# sub_sys_pdu.net
KiCad netlist of a schematic drawn in EAGLE
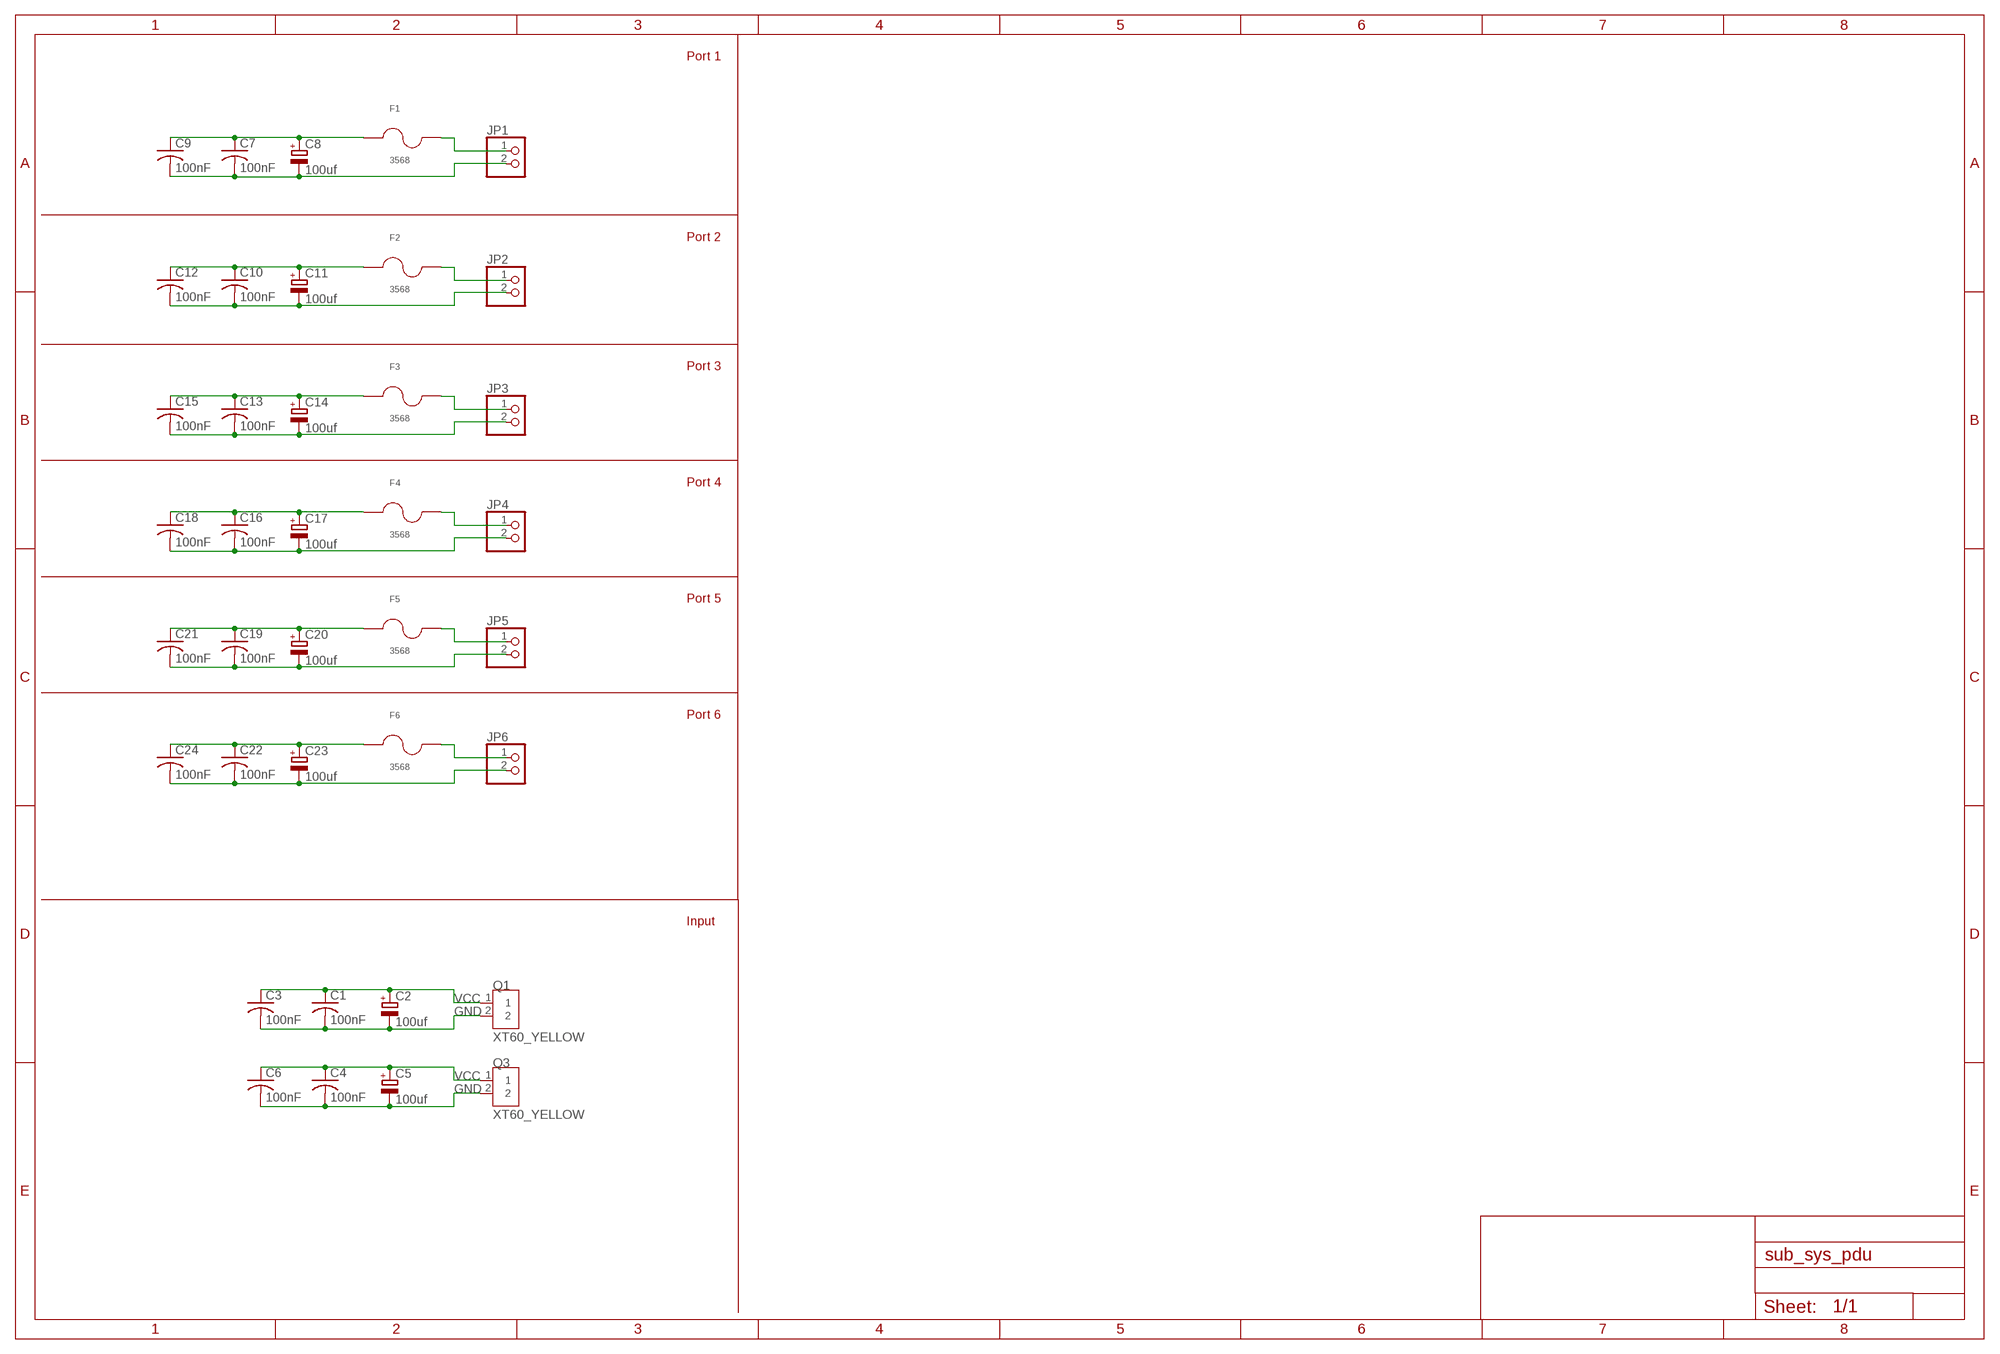
[diagram p0: schematic, sheet 1]

(export (version "E")
  (design (tool "Eeschema 10.0.6"))
  (components
    (comp (ref "C1")
      (value "100nF")
      (footprint "eagle-import:C0805")
      (libsource (lib "eagle-import") (part "C-USC0805"))
    )
    (comp (ref "C2")
      (value "100uf")
      (footprint "eagle-import:E5-10,5")
      (libsource (lib "eagle-import") (part "CPOL-EUE5-10.5"))
    )
    (comp (ref "C3")
      (value "100nF")
      (footprint "eagle-import:C0805")
      (libsource (lib "eagle-import") (part "C-USC0805"))
    )
    (comp (ref "C4")
      (value "100nF")
      (footprint "eagle-import:C0805")
      (libsource (lib "eagle-import") (part "C-USC0805"))
    )
    (comp (ref "C5")
      (value "100uf")
      (footprint "eagle-import:E5-10,5")
      (libsource (lib "eagle-import") (part "CPOL-EUE5-10.5"))
    )
    (comp (ref "C6")
      (value "100nF")
      (footprint "eagle-import:C0805")
      (libsource (lib "eagle-import") (part "C-USC0805"))
    )
    (comp (ref "C7")
      (value "100nF")
      (footprint "eagle-import:C0805")
      (libsource (lib "eagle-import") (part "C-USC0805"))
    )
    (comp (ref "C8")
      (value "100uf")
      (footprint "eagle-import:E5-10,5")
      (libsource (lib "eagle-import") (part "CPOL-EUE5-10.5"))
    )
    (comp (ref "C9")
      (value "100nF")
      (footprint "eagle-import:C0805")
      (libsource (lib "eagle-import") (part "C-USC0805"))
    )
    (comp (ref "C10")
      (value "100nF")
      (footprint "eagle-import:C0805")
      (libsource (lib "eagle-import") (part "C-USC0805"))
    )
    (comp (ref "C11")
      (value "100uf")
      (footprint "eagle-import:E5-10,5")
      (libsource (lib "eagle-import") (part "CPOL-EUE5-10.5"))
    )
    (comp (ref "C12")
      (value "100nF")
      (footprint "eagle-import:C0805")
      (libsource (lib "eagle-import") (part "C-USC0805"))
    )
    (comp (ref "C13")
      (value "100nF")
      (footprint "eagle-import:C0805")
      (libsource (lib "eagle-import") (part "C-USC0805"))
    )
    (comp (ref "C14")
      (value "100uf")
      (footprint "eagle-import:E5-10,5")
      (libsource (lib "eagle-import") (part "CPOL-EUE5-10.5"))
    )
    (comp (ref "C15")
      (value "100nF")
      (footprint "eagle-import:C0805")
      (libsource (lib "eagle-import") (part "C-USC0805"))
    )
    (comp (ref "C16")
      (value "100nF")
      (footprint "eagle-import:C0805")
      (libsource (lib "eagle-import") (part "C-USC0805"))
    )
    (comp (ref "C17")
      (value "100uf")
      (footprint "eagle-import:E5-10,5")
      (libsource (lib "eagle-import") (part "CPOL-EUE5-10.5"))
    )
    (comp (ref "C18")
      (value "100nF")
      (footprint "eagle-import:C0805")
      (libsource (lib "eagle-import") (part "C-USC0805"))
    )
    (comp (ref "C19")
      (value "100nF")
      (footprint "eagle-import:C0805")
      (libsource (lib "eagle-import") (part "C-USC0805"))
    )
    (comp (ref "C20")
      (value "100uf")
      (footprint "eagle-import:E5-10,5")
      (libsource (lib "eagle-import") (part "CPOL-EUE5-10.5"))
    )
    (comp (ref "C21")
      (value "100nF")
      (footprint "eagle-import:C0805")
      (libsource (lib "eagle-import") (part "C-USC0805"))
    )
    (comp (ref "C22")
      (value "100nF")
      (footprint "eagle-import:C0805")
      (libsource (lib "eagle-import") (part "C-USC0805"))
    )
    (comp (ref "C23")
      (value "100uf")
      (footprint "eagle-import:E5-10,5")
      (libsource (lib "eagle-import") (part "CPOL-EUE5-10.5"))
    )
    (comp (ref "C24")
      (value "100nF")
      (footprint "eagle-import:C0805")
      (libsource (lib "eagle-import") (part "C-USC0805"))
    )
    (comp (ref "F1")
      (value "3568")
      (footprint "eagle-import:FUSE_3568")
      (fields (field (name "MF") "Adafruit Industries"))
      (libsource (lib "eagle-import") (part "3568"))
    )
    (comp (ref "F2")
      (value "3568")
      (footprint "eagle-import:FUSE_3568")
      (fields (field (name "MF") "Adafruit Industries"))
      (libsource (lib "eagle-import") (part "3568"))
    )
    (comp (ref "F3")
      (value "3568")
      (footprint "eagle-import:FUSE_3568")
      (fields (field (name "MF") "Adafruit Industries"))
      (libsource (lib "eagle-import") (part "3568"))
    )
    (comp (ref "F4")
      (value "3568")
      (footprint "eagle-import:FUSE_3568")
      (fields (field (name "MF") "Adafruit Industries"))
      (libsource (lib "eagle-import") (part "3568"))
    )
    (comp (ref "F5")
      (value "3568")
      (footprint "eagle-import:FUSE_3568")
      (fields (field (name "MF") "Adafruit Industries"))
      (libsource (lib "eagle-import") (part "3568"))
    )
    (comp (ref "F6")
      (value "3568")
      (footprint "eagle-import:FUSE_3568")
      (fields (field (name "MF") "Adafruit Industries"))
      (libsource (lib "eagle-import") (part "3568"))
    )
    (comp (ref "JP1")
      (value "PINHD-1X2")
      (footprint "eagle-import:1X02")
      (libsource (lib "eagle-import") (part "PINHD-1X2"))
    )
    (comp (ref "JP2")
      (value "PINHD-1X2")
      (footprint "eagle-import:1X02")
      (libsource (lib "eagle-import") (part "PINHD-1X2"))
    )
    (comp (ref "JP3")
      (value "PINHD-1X2")
      (footprint "eagle-import:1X02")
      (libsource (lib "eagle-import") (part "PINHD-1X2"))
    )
    (comp (ref "JP4")
      (value "PINHD-1X2")
      (footprint "eagle-import:1X02")
      (libsource (lib "eagle-import") (part "PINHD-1X2"))
    )
    (comp (ref "JP5")
      (value "PINHD-1X2")
      (footprint "eagle-import:1X02")
      (libsource (lib "eagle-import") (part "PINHD-1X2"))
    )
    (comp (ref "JP6")
      (value "PINHD-1X2")
      (footprint "eagle-import:1X02")
      (libsource (lib "eagle-import") (part "PINHD-1X2"))
    )
    (comp (ref "Q1")
      (value "XT60_YELLOW")
      (footprint "eagle-import:AMASS_XT60PB-M")
      (fields (field (name "MF") "Pololu") (field (name "MP") "XT60 YELLOW"))
      (libsource (lib "eagle-import") (part "XT60_YELLOW"))
    )
    (comp (ref "Q3")
      (value "XT60_YELLOW")
      (footprint "eagle-import:AMASS_XT60PB-M")
      (fields (field (name "MF") "Pololu") (field (name "MP") "XT60 YELLOW"))
      (libsource (lib "eagle-import") (part "XT60_YELLOW"))
    )
  )
  (nets
    (net (code "1") (name "/GND") (class "Default")
      (node (ref "C1") (pin "2") (pinfunction "2_2") (pintype "passive"))
      (node (ref "C2") (pin "-") (pinfunction "-_-") (pintype "passive"))
      (node (ref "C3") (pin "2") (pinfunction "2_2") (pintype "passive"))
      (node (ref "C4") (pin "2") (pinfunction "2_2") (pintype "passive"))
      (node (ref "C5") (pin "-") (pinfunction "-_-") (pintype "passive"))
      (node (ref "C6") (pin "2") (pinfunction "2_2") (pintype "passive"))
      (node (ref "Q1") (pin "2") (pinfunction "2_2") (pintype "passive"))
      (node (ref "Q3") (pin "2") (pinfunction "2_2") (pintype "passive"))
    )
    (net (code "2") (name "/VCC") (class "Default")
      (node (ref "C1") (pin "1") (pinfunction "1_1") (pintype "passive"))
      (node (ref "C2") (pin "+") (pinfunction "+_+") (pintype "passive"))
      (node (ref "C3") (pin "1") (pinfunction "1_1") (pintype "passive"))
      (node (ref "C4") (pin "1") (pinfunction "1_1") (pintype "passive"))
      (node (ref "C5") (pin "+") (pinfunction "+_+") (pintype "passive"))
      (node (ref "C6") (pin "1") (pinfunction "1_1") (pintype "passive"))
      (node (ref "Q1") (pin "1") (pinfunction "1_1") (pintype "passive"))
      (node (ref "Q3") (pin "1") (pinfunction "1_1") (pintype "passive"))
    )
    (net (code "3") (name "Net-(C7-Pad1)") (class "Default")
      (node (ref "C7") (pin "1") (pinfunction "1_1") (pintype "passive"))
      (node (ref "C8") (pin "+") (pinfunction "+_+") (pintype "passive"))
      (node (ref "C9") (pin "1") (pinfunction "1_1") (pintype "passive"))
      (node (ref "F1") (pin "1") (pinfunction "1_1") (pintype "passive"))
      (node (ref "F1") (pin "3") (pinfunction "1_3") (pintype "passive"))
    )
    (net (code "4") (name "Net-(C7-Pad2)") (class "Default")
      (node (ref "C7") (pin "2") (pinfunction "2_2") (pintype "passive"))
      (node (ref "C8") (pin "-") (pinfunction "-_-") (pintype "passive"))
      (node (ref "C9") (pin "2") (pinfunction "2_2") (pintype "passive"))
      (node (ref "JP1") (pin "2") (pinfunction "2_2") (pintype "passive"))
    )
    (net (code "5") (name "Net-(C10-Pad1)") (class "Default")
      (node (ref "C10") (pin "1") (pinfunction "1_1") (pintype "passive"))
      (node (ref "C11") (pin "+") (pinfunction "+_+") (pintype "passive"))
      (node (ref "C12") (pin "1") (pinfunction "1_1") (pintype "passive"))
      (node (ref "F2") (pin "1") (pinfunction "1_1") (pintype "passive"))
      (node (ref "F2") (pin "3") (pinfunction "1_3") (pintype "passive"))
    )
    (net (code "6") (name "Net-(C10-Pad2)") (class "Default")
      (node (ref "C10") (pin "2") (pinfunction "2_2") (pintype "passive"))
      (node (ref "C11") (pin "-") (pinfunction "-_-") (pintype "passive"))
      (node (ref "C12") (pin "2") (pinfunction "2_2") (pintype "passive"))
      (node (ref "JP2") (pin "2") (pinfunction "2_2") (pintype "passive"))
    )
    (net (code "7") (name "Net-(C13-Pad1)") (class "Default")
      (node (ref "C13") (pin "1") (pinfunction "1_1") (pintype "passive"))
      (node (ref "C14") (pin "+") (pinfunction "+_+") (pintype "passive"))
      (node (ref "C15") (pin "1") (pinfunction "1_1") (pintype "passive"))
      (node (ref "F3") (pin "1") (pinfunction "1_1") (pintype "passive"))
      (node (ref "F3") (pin "3") (pinfunction "1_3") (pintype "passive"))
    )
    (net (code "8") (name "Net-(C13-Pad2)") (class "Default")
      (node (ref "C13") (pin "2") (pinfunction "2_2") (pintype "passive"))
      (node (ref "C14") (pin "-") (pinfunction "-_-") (pintype "passive"))
      (node (ref "C15") (pin "2") (pinfunction "2_2") (pintype "passive"))
      (node (ref "JP3") (pin "2") (pinfunction "2_2") (pintype "passive"))
    )
    (net (code "9") (name "Net-(C16-Pad1)") (class "Default")
      (node (ref "C16") (pin "1") (pinfunction "1_1") (pintype "passive"))
      (node (ref "C17") (pin "+") (pinfunction "+_+") (pintype "passive"))
      (node (ref "C18") (pin "1") (pinfunction "1_1") (pintype "passive"))
      (node (ref "F4") (pin "1") (pinfunction "1_1") (pintype "passive"))
      (node (ref "F4") (pin "3") (pinfunction "1_3") (pintype "passive"))
    )
    (net (code "10") (name "Net-(C16-Pad2)") (class "Default")
      (node (ref "C16") (pin "2") (pinfunction "2_2") (pintype "passive"))
      (node (ref "C17") (pin "-") (pinfunction "-_-") (pintype "passive"))
      (node (ref "C18") (pin "2") (pinfunction "2_2") (pintype "passive"))
      (node (ref "JP4") (pin "2") (pinfunction "2_2") (pintype "passive"))
    )
    (net (code "11") (name "Net-(C19-Pad1)") (class "Default")
      (node (ref "C19") (pin "1") (pinfunction "1_1") (pintype "passive"))
      (node (ref "C20") (pin "+") (pinfunction "+_+") (pintype "passive"))
      (node (ref "C21") (pin "1") (pinfunction "1_1") (pintype "passive"))
      (node (ref "F5") (pin "1") (pinfunction "1_1") (pintype "passive"))
      (node (ref "F5") (pin "3") (pinfunction "1_3") (pintype "passive"))
    )
    (net (code "12") (name "Net-(C19-Pad2)") (class "Default")
      (node (ref "C19") (pin "2") (pinfunction "2_2") (pintype "passive"))
      (node (ref "C20") (pin "-") (pinfunction "-_-") (pintype "passive"))
      (node (ref "C21") (pin "2") (pinfunction "2_2") (pintype "passive"))
      (node (ref "JP5") (pin "2") (pinfunction "2_2") (pintype "passive"))
    )
    (net (code "13") (name "Net-(C22-Pad1)") (class "Default")
      (node (ref "C22") (pin "1") (pinfunction "1_1") (pintype "passive"))
      (node (ref "C23") (pin "+") (pinfunction "+_+") (pintype "passive"))
      (node (ref "C24") (pin "1") (pinfunction "1_1") (pintype "passive"))
      (node (ref "F6") (pin "1") (pinfunction "1_1") (pintype "passive"))
      (node (ref "F6") (pin "3") (pinfunction "1_3") (pintype "passive"))
    )
    (net (code "14") (name "Net-(C22-Pad2)") (class "Default")
      (node (ref "C22") (pin "2") (pinfunction "2_2") (pintype "passive"))
      (node (ref "C23") (pin "-") (pinfunction "-_-") (pintype "passive"))
      (node (ref "C24") (pin "2") (pinfunction "2_2") (pintype "passive"))
      (node (ref "JP6") (pin "2") (pinfunction "2_2") (pintype "passive"))
    )
    (net (code "15") (name "Net-(F1-2-Pad4)") (class "Default")
      (node (ref "F1") (pin "2") (pinfunction "2_2") (pintype "passive"))
      (node (ref "F1") (pin "4") (pinfunction "2_4") (pintype "passive"))
      (node (ref "JP1") (pin "1") (pinfunction "1_1") (pintype "passive"))
    )
    (net (code "16") (name "Net-(F2-2-Pad4)") (class "Default")
      (node (ref "F2") (pin "2") (pinfunction "2_2") (pintype "passive"))
      (node (ref "F2") (pin "4") (pinfunction "2_4") (pintype "passive"))
      (node (ref "JP2") (pin "1") (pinfunction "1_1") (pintype "passive"))
    )
    (net (code "17") (name "Net-(F3-2-Pad4)") (class "Default")
      (node (ref "F3") (pin "2") (pinfunction "2_2") (pintype "passive"))
      (node (ref "F3") (pin "4") (pinfunction "2_4") (pintype "passive"))
      (node (ref "JP3") (pin "1") (pinfunction "1_1") (pintype "passive"))
    )
    (net (code "18") (name "Net-(F4-2-Pad4)") (class "Default")
      (node (ref "F4") (pin "2") (pinfunction "2_2") (pintype "passive"))
      (node (ref "F4") (pin "4") (pinfunction "2_4") (pintype "passive"))
      (node (ref "JP4") (pin "1") (pinfunction "1_1") (pintype "passive"))
    )
    (net (code "19") (name "Net-(F5-2-Pad4)") (class "Default")
      (node (ref "F5") (pin "2") (pinfunction "2_2") (pintype "passive"))
      (node (ref "F5") (pin "4") (pinfunction "2_4") (pintype "passive"))
      (node (ref "JP5") (pin "1") (pinfunction "1_1") (pintype "passive"))
    )
    (net (code "20") (name "Net-(F6-2-Pad4)") (class "Default")
      (node (ref "F6") (pin "2") (pinfunction "2_2") (pintype "passive"))
      (node (ref "F6") (pin "4") (pinfunction "2_4") (pintype "passive"))
      (node (ref "JP6") (pin "1") (pinfunction "1_1") (pintype "passive"))
    )
  )
)
